# arm-pro-mini-tester.net
KiCad netlist of a schematic drawn in EAGLE
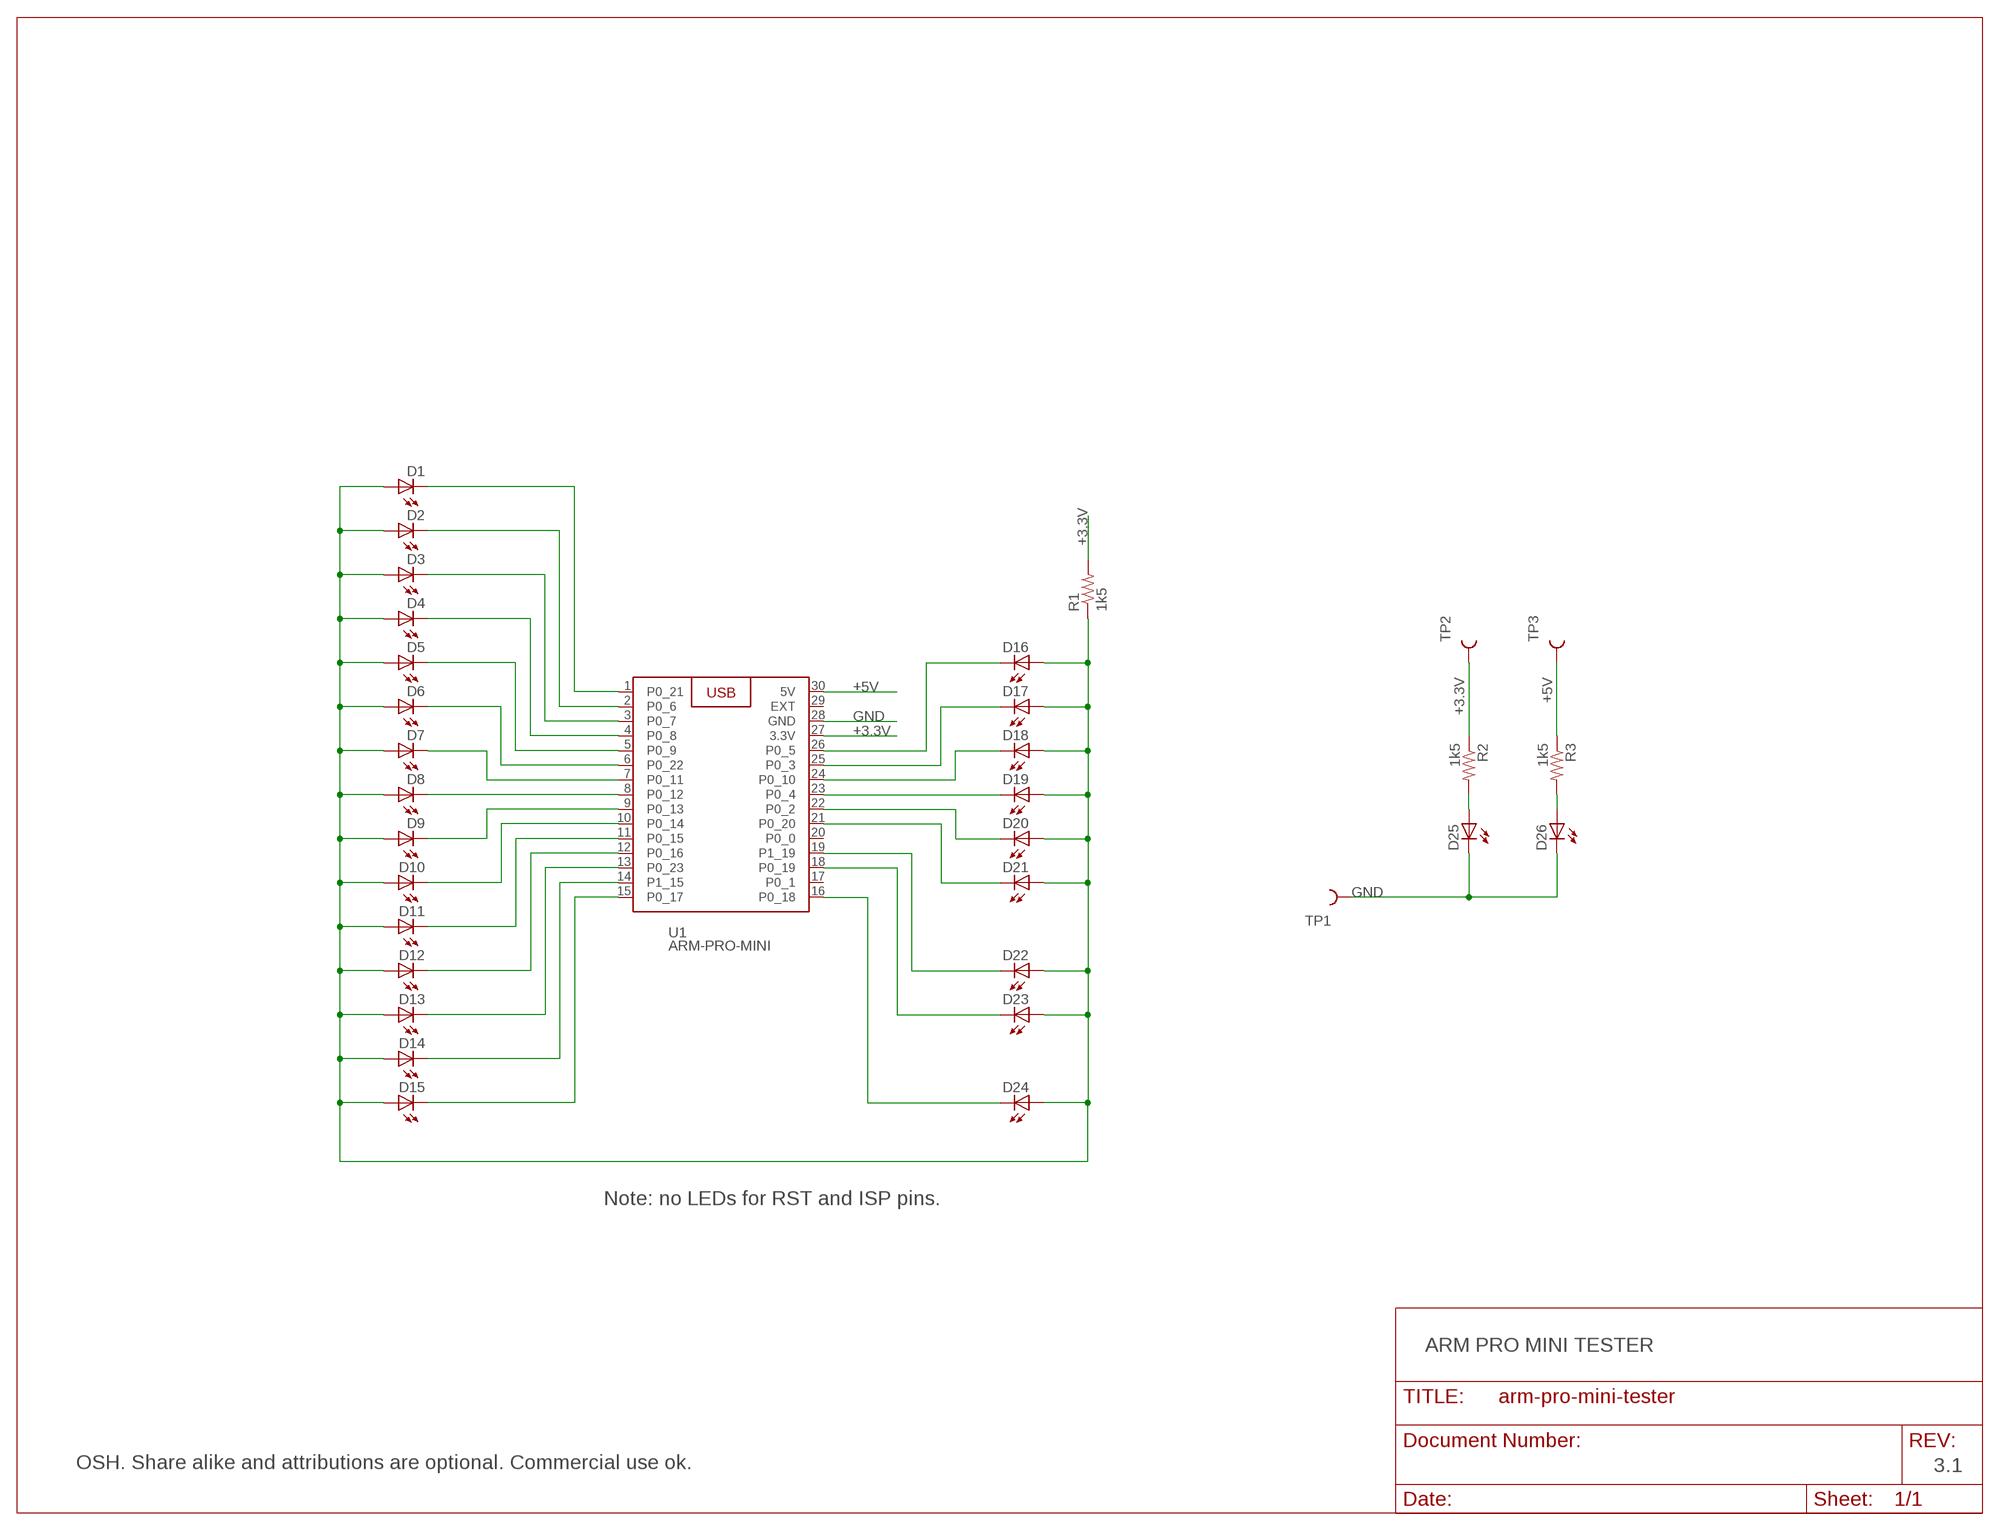
[diagram p0: schematic, sheet 1]

(export (version "E")
  (design (tool "Eeschema 10.0.6"))
  (components
    (comp (ref "D1")
      (value "LED")
      (footprint "eagle-import:LED0603")
      (libsource (lib "eagle-import") (part "LED"))
    )
    (comp (ref "D2")
      (value "LED")
      (footprint "eagle-import:LED0603")
      (libsource (lib "eagle-import") (part "LED"))
    )
    (comp (ref "D3")
      (value "LED")
      (footprint "eagle-import:LED0603")
      (libsource (lib "eagle-import") (part "LED"))
    )
    (comp (ref "D4")
      (value "LED")
      (footprint "eagle-import:LED0603")
      (libsource (lib "eagle-import") (part "LED"))
    )
    (comp (ref "D5")
      (value "LED")
      (footprint "eagle-import:LED0603")
      (libsource (lib "eagle-import") (part "LED"))
    )
    (comp (ref "D6")
      (value "LED")
      (footprint "eagle-import:LED0603")
      (libsource (lib "eagle-import") (part "LED"))
    )
    (comp (ref "D7")
      (value "LED")
      (footprint "eagle-import:LED0603")
      (libsource (lib "eagle-import") (part "LED"))
    )
    (comp (ref "D8")
      (value "LED")
      (footprint "eagle-import:LED0603")
      (libsource (lib "eagle-import") (part "LED"))
    )
    (comp (ref "D9")
      (value "LED")
      (footprint "eagle-import:LED0603")
      (libsource (lib "eagle-import") (part "LED"))
    )
    (comp (ref "D10")
      (value "LED")
      (footprint "eagle-import:LED0603")
      (libsource (lib "eagle-import") (part "LED"))
    )
    (comp (ref "D11")
      (value "LED")
      (footprint "eagle-import:LED0603")
      (libsource (lib "eagle-import") (part "LED"))
    )
    (comp (ref "D12")
      (value "LED")
      (footprint "eagle-import:LED0603")
      (libsource (lib "eagle-import") (part "LED"))
    )
    (comp (ref "D13")
      (value "LED")
      (footprint "eagle-import:LED0603")
      (libsource (lib "eagle-import") (part "LED"))
    )
    (comp (ref "D14")
      (value "LED")
      (footprint "eagle-import:LED0603")
      (libsource (lib "eagle-import") (part "LED"))
    )
    (comp (ref "D15")
      (value "LED")
      (footprint "eagle-import:LED0603")
      (libsource (lib "eagle-import") (part "LED"))
    )
    (comp (ref "D16")
      (value "LED")
      (footprint "eagle-import:LED0603")
      (libsource (lib "eagle-import") (part "LED"))
    )
    (comp (ref "D17")
      (value "LED")
      (footprint "eagle-import:LED0603")
      (libsource (lib "eagle-import") (part "LED"))
    )
    (comp (ref "D18")
      (value "LED")
      (footprint "eagle-import:LED0603")
      (libsource (lib "eagle-import") (part "LED"))
    )
    (comp (ref "D19")
      (value "LED")
      (footprint "eagle-import:LED0603")
      (libsource (lib "eagle-import") (part "LED"))
    )
    (comp (ref "D20")
      (value "LED")
      (footprint "eagle-import:LED0603")
      (libsource (lib "eagle-import") (part "LED"))
    )
    (comp (ref "D21")
      (value "LED")
      (footprint "eagle-import:LED0603")
      (libsource (lib "eagle-import") (part "LED"))
    )
    (comp (ref "D22")
      (value "LED")
      (footprint "eagle-import:LED0603")
      (libsource (lib "eagle-import") (part "LED"))
    )
    (comp (ref "D23")
      (value "LED")
      (footprint "eagle-import:LED0603")
      (libsource (lib "eagle-import") (part "LED"))
    )
    (comp (ref "D24")
      (value "LED")
      (footprint "eagle-import:LED0603")
      (libsource (lib "eagle-import") (part "LED"))
    )
    (comp (ref "D25")
      (value "LED")
      (footprint "eagle-import:LED0603")
      (libsource (lib "eagle-import") (part "LED"))
    )
    (comp (ref "D26")
      (value "LED")
      (footprint "eagle-import:LED0603")
      (libsource (lib "eagle-import") (part "LED"))
    )
    (comp (ref "R1")
      (value "1k5")
      (footprint "eagle-import:R0603")
      (libsource (lib "eagle-import") (part "R-US_R0603"))
    )
    (comp (ref "R2")
      (value "1k5")
      (footprint "eagle-import:R0603")
      (libsource (lib "eagle-import") (part "R-US_R0603"))
    )
    (comp (ref "R3")
      (value "1k5")
      (footprint "eagle-import:R0603")
      (libsource (lib "eagle-import") (part "R-US_R0603"))
    )
    (comp (ref "TP1")
      (value "TEST-POINT")
      (footprint "eagle-import:TEST-POINT")
      (libsource (lib "eagle-import") (part "TEST-POINT"))
    )
    (comp (ref "TP2")
      (value "TEST-POINT")
      (footprint "eagle-import:TEST-POINT")
      (libsource (lib "eagle-import") (part "TEST-POINT"))
    )
    (comp (ref "TP3")
      (value "TEST-POINT")
      (footprint "eagle-import:TEST-POINT")
      (libsource (lib "eagle-import") (part "TEST-POINT"))
    )
    (comp (ref "U1")
      (value "ARM-PRO-MINI")
      (footprint "eagle-import:ARM-PRO-MINI")
      (libsource (lib "eagle-import") (part "ARM-PRO-MINI"))
    )
  )
  (nets
    (net (code "1") (name "/+3.3V") (class "Default")
      (node (ref "R1") (pin "2") (pinfunction "2_2") (pintype "passive"))
      (node (ref "R2") (pin "1") (pinfunction "1_1") (pintype "passive"))
      (node (ref "TP2") (pin "A") (pinfunction "TP_A") (pintype "passive"))
      (node (ref "TP2") (pin "B") (pinfunction "TP_B") (pintype "passive"))
      (node (ref "U1") (pin "27") (pinfunction "3.3V_27") (pintype "passive"))
    )
    (net (code "2") (name "/+5V") (class "Default")
      (node (ref "R3") (pin "1") (pinfunction "1_1") (pintype "passive"))
      (node (ref "TP3") (pin "A") (pinfunction "TP_A") (pintype "passive"))
      (node (ref "TP3") (pin "B") (pinfunction "TP_B") (pintype "passive"))
      (node (ref "U1") (pin "30") (pinfunction "5V_30") (pintype "passive"))
    )
    (net (code "3") (name "/GND") (class "Default")
      (node (ref "D25") (pin "C") (pinfunction "C_C") (pintype "passive"))
      (node (ref "D26") (pin "C") (pinfunction "C_C") (pintype "passive"))
      (node (ref "TP1") (pin "A") (pinfunction "TP_A") (pintype "passive"))
      (node (ref "TP1") (pin "B") (pinfunction "TP_B") (pintype "passive"))
      (node (ref "U1") (pin "28") (pinfunction "GND_28") (pintype "passive"))
    )
    (net (code "4") (name "Net-(D1-PadA)") (class "Default")
      (node (ref "D1") (pin "A") (pinfunction "A_A") (pintype "passive"))
      (node (ref "D10") (pin "A") (pinfunction "A_A") (pintype "passive"))
      (node (ref "D11") (pin "A") (pinfunction "A_A") (pintype "passive"))
      (node (ref "D12") (pin "A") (pinfunction "A_A") (pintype "passive"))
      (node (ref "D13") (pin "A") (pinfunction "A_A") (pintype "passive"))
      (node (ref "D14") (pin "A") (pinfunction "A_A") (pintype "passive"))
      (node (ref "D15") (pin "A") (pinfunction "A_A") (pintype "passive"))
      (node (ref "D16") (pin "A") (pinfunction "A_A") (pintype "passive"))
      (node (ref "D17") (pin "A") (pinfunction "A_A") (pintype "passive"))
      (node (ref "D18") (pin "A") (pinfunction "A_A") (pintype "passive"))
      (node (ref "D19") (pin "A") (pinfunction "A_A") (pintype "passive"))
      (node (ref "D2") (pin "A") (pinfunction "A_A") (pintype "passive"))
      (node (ref "D20") (pin "A") (pinfunction "A_A") (pintype "passive"))
      (node (ref "D21") (pin "A") (pinfunction "A_A") (pintype "passive"))
      (node (ref "D22") (pin "A") (pinfunction "A_A") (pintype "passive"))
      (node (ref "D23") (pin "A") (pinfunction "A_A") (pintype "passive"))
      (node (ref "D24") (pin "A") (pinfunction "A_A") (pintype "passive"))
      (node (ref "D3") (pin "A") (pinfunction "A_A") (pintype "passive"))
      (node (ref "D4") (pin "A") (pinfunction "A_A") (pintype "passive"))
      (node (ref "D5") (pin "A") (pinfunction "A_A") (pintype "passive"))
      (node (ref "D6") (pin "A") (pinfunction "A_A") (pintype "passive"))
      (node (ref "D7") (pin "A") (pinfunction "A_A") (pintype "passive"))
      (node (ref "D8") (pin "A") (pinfunction "A_A") (pintype "passive"))
      (node (ref "D9") (pin "A") (pinfunction "A_A") (pintype "passive"))
      (node (ref "R1") (pin "1") (pinfunction "1_1") (pintype "passive"))
    )
    (net (code "5") (name "Net-(D25-PadA)") (class "Default")
      (node (ref "D25") (pin "A") (pinfunction "A_A") (pintype "passive"))
      (node (ref "R2") (pin "2") (pinfunction "2_2") (pintype "passive"))
    )
    (net (code "6") (name "Net-(D26-PadA)") (class "Default")
      (node (ref "D26") (pin "A") (pinfunction "A_A") (pintype "passive"))
      (node (ref "R3") (pin "2") (pinfunction "2_2") (pintype "passive"))
    )
    (net (code "7") (name "Net-(U1-P0_2)") (class "Default")
      (node (ref "D20") (pin "C") (pinfunction "C_C") (pintype "passive"))
      (node (ref "U1") (pin "22") (pinfunction "P0_2_22") (pintype "passive"))
    )
    (net (code "8") (name "Net-(U1-P0_3)") (class "Default")
      (node (ref "D17") (pin "C") (pinfunction "C_C") (pintype "passive"))
      (node (ref "U1") (pin "25") (pinfunction "P0_3_25") (pintype "passive"))
    )
    (net (code "9") (name "Net-(U1-P0_4)") (class "Default")
      (node (ref "D19") (pin "C") (pinfunction "C_C") (pintype "passive"))
      (node (ref "U1") (pin "23") (pinfunction "P0_4_23") (pintype "passive"))
    )
    (net (code "10") (name "Net-(U1-P0_5)") (class "Default")
      (node (ref "D16") (pin "C") (pinfunction "C_C") (pintype "passive"))
      (node (ref "U1") (pin "26") (pinfunction "P0_5_26") (pintype "passive"))
    )
    (net (code "11") (name "Net-(U1-P0_6)") (class "Default")
      (node (ref "D2") (pin "C") (pinfunction "C_C") (pintype "passive"))
      (node (ref "U1") (pin "2") (pinfunction "P0_6_2") (pintype "passive"))
    )
    (net (code "12") (name "Net-(U1-P0_7)") (class "Default")
      (node (ref "D3") (pin "C") (pinfunction "C_C") (pintype "passive"))
      (node (ref "U1") (pin "3") (pinfunction "P0_7_3") (pintype "passive"))
    )
    (net (code "13") (name "Net-(U1-P0_8)") (class "Default")
      (node (ref "D4") (pin "C") (pinfunction "C_C") (pintype "passive"))
      (node (ref "U1") (pin "4") (pinfunction "P0_8_4") (pintype "passive"))
    )
    (net (code "14") (name "Net-(U1-P0_9)") (class "Default")
      (node (ref "D5") (pin "C") (pinfunction "C_C") (pintype "passive"))
      (node (ref "U1") (pin "5") (pinfunction "P0_9_5") (pintype "passive"))
    )
    (net (code "15") (name "Net-(U1-P0_10)") (class "Default")
      (node (ref "D18") (pin "C") (pinfunction "C_C") (pintype "passive"))
      (node (ref "U1") (pin "24") (pinfunction "P0_10_24") (pintype "passive"))
    )
    (net (code "16") (name "Net-(U1-P0_11)") (class "Default")
      (node (ref "D7") (pin "C") (pinfunction "C_C") (pintype "passive"))
      (node (ref "U1") (pin "7") (pinfunction "P0_11_7") (pintype "passive"))
    )
    (net (code "17") (name "Net-(U1-P0_12)") (class "Default")
      (node (ref "D8") (pin "C") (pinfunction "C_C") (pintype "passive"))
      (node (ref "U1") (pin "8") (pinfunction "P0_12_8") (pintype "passive"))
    )
    (net (code "18") (name "Net-(U1-P0_13)") (class "Default")
      (node (ref "D9") (pin "C") (pinfunction "C_C") (pintype "passive"))
      (node (ref "U1") (pin "9") (pinfunction "P0_13_9") (pintype "passive"))
    )
    (net (code "19") (name "Net-(U1-P0_14)") (class "Default")
      (node (ref "D10") (pin "C") (pinfunction "C_C") (pintype "passive"))
      (node (ref "U1") (pin "10") (pinfunction "P0_14_10") (pintype "passive"))
    )
    (net (code "20") (name "Net-(U1-P0_15)") (class "Default")
      (node (ref "D11") (pin "C") (pinfunction "C_C") (pintype "passive"))
      (node (ref "U1") (pin "11") (pinfunction "P0_15_11") (pintype "passive"))
    )
    (net (code "21") (name "Net-(U1-P0_16)") (class "Default")
      (node (ref "D12") (pin "C") (pinfunction "C_C") (pintype "passive"))
      (node (ref "U1") (pin "12") (pinfunction "P0_16_12") (pintype "passive"))
    )
    (net (code "22") (name "Net-(U1-P0_17)") (class "Default")
      (node (ref "D15") (pin "C") (pinfunction "C_C") (pintype "passive"))
      (node (ref "U1") (pin "15") (pinfunction "P0_17_15") (pintype "passive"))
    )
    (net (code "23") (name "Net-(U1-P0_18)") (class "Default")
      (node (ref "D24") (pin "C") (pinfunction "C_C") (pintype "passive"))
      (node (ref "U1") (pin "16") (pinfunction "P0_18_16") (pintype "passive"))
    )
    (net (code "24") (name "Net-(U1-P0_19)") (class "Default")
      (node (ref "D23") (pin "C") (pinfunction "C_C") (pintype "passive"))
      (node (ref "U1") (pin "18") (pinfunction "P0_19_18") (pintype "passive"))
    )
    (net (code "25") (name "Net-(U1-P0_20)") (class "Default")
      (node (ref "D21") (pin "C") (pinfunction "C_C") (pintype "passive"))
      (node (ref "U1") (pin "21") (pinfunction "P0_20_21") (pintype "passive"))
    )
    (net (code "26") (name "Net-(U1-P0_21)") (class "Default")
      (node (ref "D1") (pin "C") (pinfunction "C_C") (pintype "passive"))
      (node (ref "U1") (pin "1") (pinfunction "P0_21_1") (pintype "passive"))
    )
    (net (code "27") (name "Net-(U1-P0_22)") (class "Default")
      (node (ref "D6") (pin "C") (pinfunction "C_C") (pintype "passive"))
      (node (ref "U1") (pin "6") (pinfunction "P0_22_6") (pintype "passive"))
    )
    (net (code "28") (name "Net-(U1-P0_23)") (class "Default")
      (node (ref "D13") (pin "C") (pinfunction "C_C") (pintype "passive"))
      (node (ref "U1") (pin "13") (pinfunction "P0_23_13") (pintype "passive"))
    )
    (net (code "29") (name "Net-(U1-P1_15)") (class "Default")
      (node (ref "D14") (pin "C") (pinfunction "C_C") (pintype "passive"))
      (node (ref "U1") (pin "14") (pinfunction "P1_15_14") (pintype "passive"))
    )
    (net (code "30") (name "Net-(U1-P1_19)") (class "Default")
      (node (ref "D22") (pin "C") (pinfunction "C_C") (pintype "passive"))
      (node (ref "U1") (pin "19") (pinfunction "P1_19_19") (pintype "passive"))
    )
    (net (code "31") (name "unconnected-(U1-EXT-Pad29)") (class "Default")
      (node (ref "U1") (pin "29") (pinfunction "EXT_29") (pintype "passive"))
    )
    (net (code "32") (name "unconnected-(U1-P0_0-Pad20)") (class "Default")
      (node (ref "U1") (pin "20") (pinfunction "P0_0_20") (pintype "passive"))
    )
    (net (code "33") (name "unconnected-(U1-P0_1-Pad17)") (class "Default")
      (node (ref "U1") (pin "17") (pinfunction "P0_1_17") (pintype "passive"))
    )
  )
)
